# nixie_main_controller_board_0_2_3.net
KiCad netlist of a schematic drawn in EAGLE
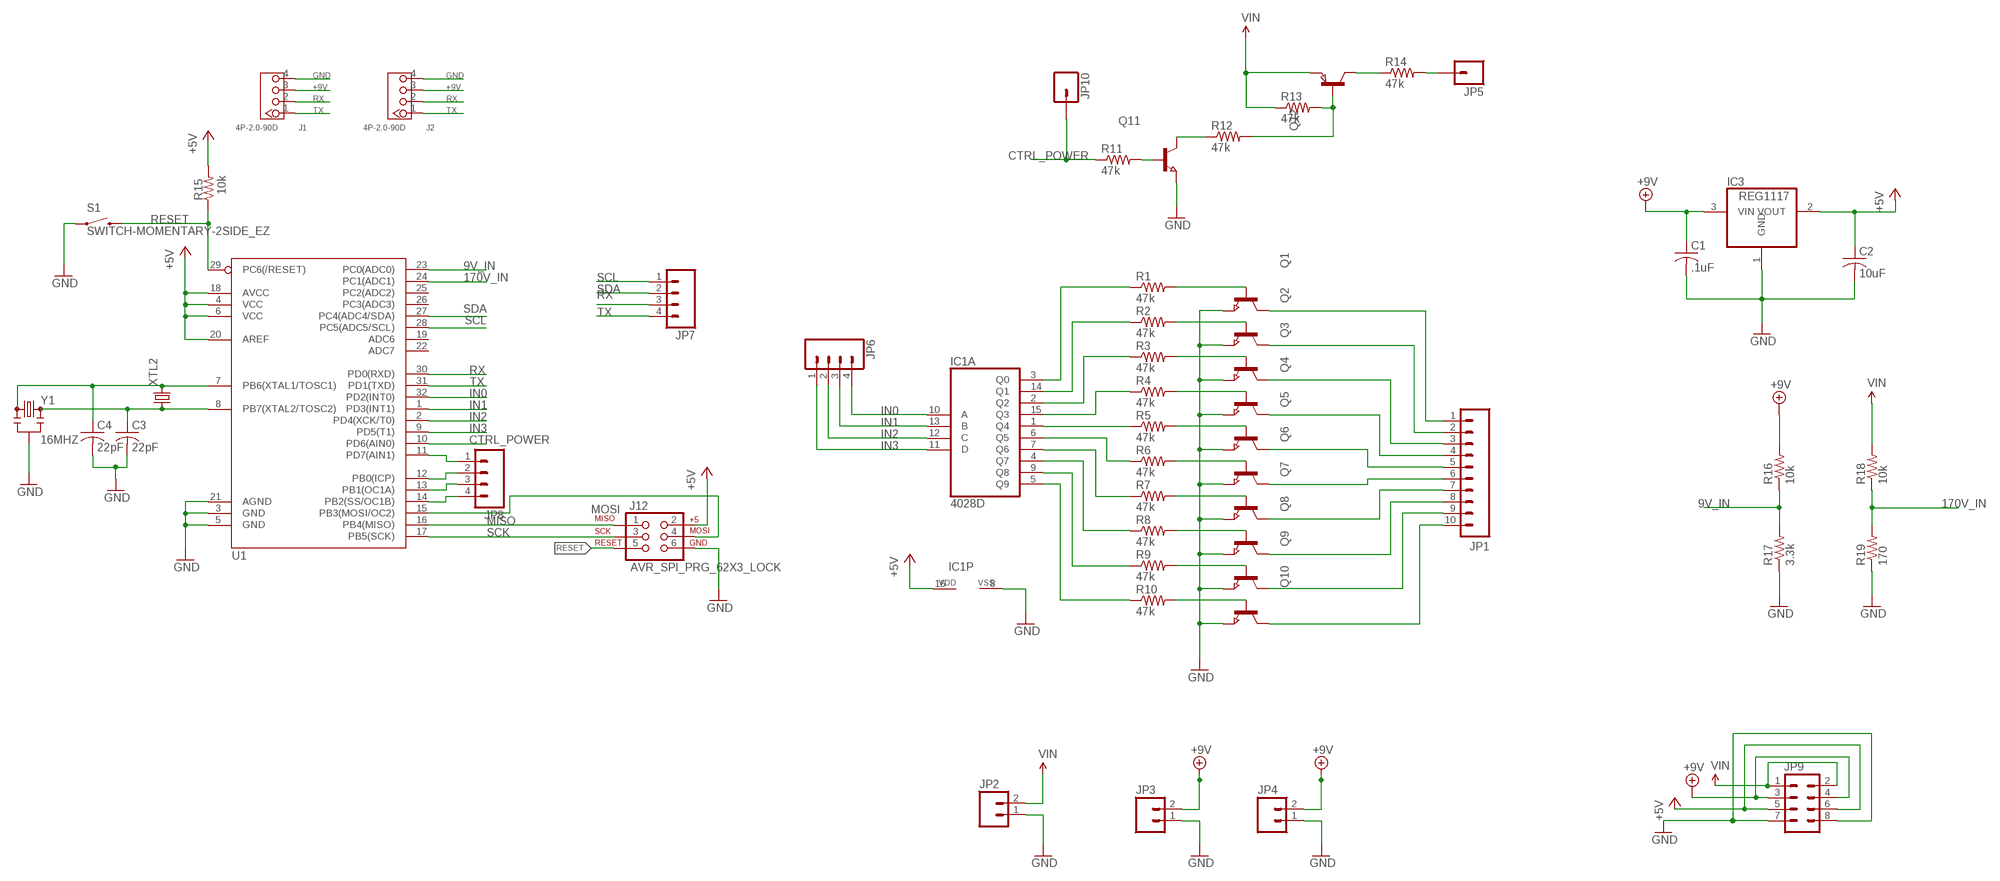
[diagram p0: schematic, sheet 1]

(export (version "E")
  (design (tool "Eeschema 10.0.6"))
  (components
    (comp (ref "C1")
      (value ".1uF")
      (footprint "eagle-import:C0603")
      (libsource (lib "eagle-import") (part "C-USC0603"))
    )
    (comp (ref "C2")
      (value "10uF")
      (footprint "eagle-import:C0805")
      (libsource (lib "eagle-import") (part "C-USC0805"))
    )
    (comp (ref "C3")
      (value "22pF")
      (footprint "eagle-import:C0603")
      (libsource (lib "eagle-import") (part "C-USC0603"))
    )
    (comp (ref "C4")
      (value "22pF")
      (footprint "eagle-import:C0603")
      (libsource (lib "eagle-import") (part "C-USC0603"))
    )
    (comp (ref "IC1")
      (value "4028D")
      (footprint "eagle-import:SO16")
      (libsource (lib "eagle-import") (part "4028D"))
    )
    (comp (ref "IC3")
      (value "REG1117")
      (footprint "eagle-import:SOT223")
      (libsource (lib "eagle-import") (part "REG1117"))
    )
    (comp (ref "J1")
      (value "4P-2.0-90D")
      (footprint "eagle-import:HW4-2.0-90D")
      (libsource (lib "eagle-import") (part "GROVE-CONNECTOR-DIP-90D(4P-2.0)"))
    )
    (comp (ref "J2")
      (value "4P-2.0-90D")
      (footprint "eagle-import:HW4-2.0-90D")
      (libsource (lib "eagle-import") (part "GROVE-CONNECTOR-DIP-90D(4P-2.0)"))
    )
    (comp (ref "J12")
      (value "AVR_SPI_PRG_62X3_LOCK")
      (footprint "eagle-import:2X3_LOCK")
      (libsource (lib "eagle-import") (part "AVR_SPI_PRG_62X3_LOCK"))
    )
    (comp (ref "JP1")
      (value "M10LOCK")
      (footprint "eagle-import:1X10_LOCK")
      (libsource (lib "eagle-import") (part "M10LOCK"))
    )
    (comp (ref "JP2")
      (value "M02LOCK")
      (footprint "eagle-import:1X02_LOCK")
      (libsource (lib "eagle-import") (part "M02LOCK"))
    )
    (comp (ref "JP3")
      (value "M02LOCK")
      (footprint "eagle-import:1X02_LOCK")
      (libsource (lib "eagle-import") (part "M02LOCK"))
    )
    (comp (ref "JP4")
      (value "M02LOCK")
      (footprint "eagle-import:1X02_LOCK")
      (libsource (lib "eagle-import") (part "M02LOCK"))
    )
    (comp (ref "JP5")
      (value "M01PTH")
      (footprint "eagle-import:1X01")
      (libsource (lib "eagle-import") (part "M01PTH"))
    )
    (comp (ref "JP6")
      (value "M04PTH")
      (footprint "eagle-import:1X04")
      (libsource (lib "eagle-import") (part "M04PTH"))
    )
    (comp (ref "JP7")
      (value "M04PTH")
      (footprint "eagle-import:1X04")
      (libsource (lib "eagle-import") (part "M04PTH"))
    )
    (comp (ref "JP8")
      (value "M04PTH")
      (footprint "eagle-import:1X04")
      (libsource (lib "eagle-import") (part "M04PTH"))
    )
    (comp (ref "JP9")
      (value "M04X2")
      (footprint "eagle-import:2X4")
      (libsource (lib "eagle-import") (part "M04X2"))
    )
    (comp (ref "JP10")
      (value "M01PTH")
      (footprint "eagle-import:1X01")
      (libsource (lib "eagle-import") (part "M01PTH"))
    )
    (comp (ref "Q1")
      (value "NPN-TRANSISTOR_SOT23")
      (footprint "eagle-import:SOT23")
      (libsource (lib "eagle-import") (part "NPN-TRANSISTOR_SOT23"))
    )
    (comp (ref "Q2")
      (value "NPN-TRANSISTOR_SOT23")
      (footprint "eagle-import:SOT23")
      (libsource (lib "eagle-import") (part "NPN-TRANSISTOR_SOT23"))
    )
    (comp (ref "Q3")
      (value "NPN-TRANSISTOR_SOT23")
      (footprint "eagle-import:SOT23")
      (libsource (lib "eagle-import") (part "NPN-TRANSISTOR_SOT23"))
    )
    (comp (ref "Q4")
      (value "NPN-TRANSISTOR_SOT23")
      (footprint "eagle-import:SOT23")
      (libsource (lib "eagle-import") (part "NPN-TRANSISTOR_SOT23"))
    )
    (comp (ref "Q5")
      (value "NPN-TRANSISTOR_SOT23")
      (footprint "eagle-import:SOT23")
      (libsource (lib "eagle-import") (part "NPN-TRANSISTOR_SOT23"))
    )
    (comp (ref "Q6")
      (value "NPN-TRANSISTOR_SOT23")
      (footprint "eagle-import:SOT23")
      (libsource (lib "eagle-import") (part "NPN-TRANSISTOR_SOT23"))
    )
    (comp (ref "Q7")
      (value "NPN-TRANSISTOR_SOT23")
      (footprint "eagle-import:SOT23")
      (libsource (lib "eagle-import") (part "NPN-TRANSISTOR_SOT23"))
    )
    (comp (ref "Q8")
      (value "NPN-TRANSISTOR_SOT23")
      (footprint "eagle-import:SOT23")
      (libsource (lib "eagle-import") (part "NPN-TRANSISTOR_SOT23"))
    )
    (comp (ref "Q9")
      (value "NPN-TRANSISTOR_SOT23")
      (footprint "eagle-import:SOT23")
      (libsource (lib "eagle-import") (part "NPN-TRANSISTOR_SOT23"))
    )
    (comp (ref "Q10")
      (value "NPN-TRANSISTOR_SOT23")
      (footprint "eagle-import:SOT23")
      (libsource (lib "eagle-import") (part "NPN-TRANSISTOR_SOT23"))
    )
    (comp (ref "Q11")
      (value "NPN-TRANSISTOR_SOT23")
      (footprint "eagle-import:SOT23")
      (libsource (lib "eagle-import") (part "NPN-TRANSISTOR_SOT23"))
    )
    (comp (ref "Q12")
      (value "PNP-TRANSISTOR_SOT23")
      (footprint "eagle-import:SOT23")
      (libsource (lib "eagle-import") (part "PNP-TRANSISTOR_SOT23"))
    )
    (comp (ref "R1")
      (value "47k")
      (footprint "eagle-import:R0603")
      (libsource (lib "eagle-import") (part "rcl_R-US_R0603"))
    )
    (comp (ref "R2")
      (value "47k")
      (footprint "eagle-import:R0603")
      (libsource (lib "eagle-import") (part "rcl_R-US_R0603"))
    )
    (comp (ref "R3")
      (value "47k")
      (footprint "eagle-import:R0603")
      (libsource (lib "eagle-import") (part "rcl_R-US_R0603"))
    )
    (comp (ref "R4")
      (value "47k")
      (footprint "eagle-import:R0603")
      (libsource (lib "eagle-import") (part "rcl_R-US_R0603"))
    )
    (comp (ref "R5")
      (value "47k")
      (footprint "eagle-import:R0603")
      (libsource (lib "eagle-import") (part "rcl_R-US_R0603"))
    )
    (comp (ref "R6")
      (value "47k")
      (footprint "eagle-import:R0603")
      (libsource (lib "eagle-import") (part "rcl_R-US_R0603"))
    )
    (comp (ref "R7")
      (value "47k")
      (footprint "eagle-import:R0603")
      (libsource (lib "eagle-import") (part "rcl_R-US_R0603"))
    )
    (comp (ref "R8")
      (value "47k")
      (footprint "eagle-import:R0603")
      (libsource (lib "eagle-import") (part "rcl_R-US_R0603"))
    )
    (comp (ref "R9")
      (value "47k")
      (footprint "eagle-import:R0603")
      (libsource (lib "eagle-import") (part "rcl_R-US_R0603"))
    )
    (comp (ref "R10")
      (value "47k")
      (footprint "eagle-import:R0603")
      (libsource (lib "eagle-import") (part "rcl_R-US_R0603"))
    )
    (comp (ref "R11")
      (value "47k")
      (footprint "eagle-import:R0603")
      (libsource (lib "eagle-import") (part "rcl_R-US_R0603"))
    )
    (comp (ref "R12")
      (value "47k")
      (footprint "eagle-import:R0603")
      (libsource (lib "eagle-import") (part "rcl_R-US_R0603"))
    )
    (comp (ref "R13")
      (value "47k")
      (footprint "eagle-import:R0603")
      (libsource (lib "eagle-import") (part "rcl_R-US_R0603"))
    )
    (comp (ref "R14")
      (value "47k")
      (footprint "eagle-import:R0603")
      (libsource (lib "eagle-import") (part "rcl_R-US_R0603"))
    )
    (comp (ref "R15")
      (value "10k")
      (footprint "eagle-import:0603")
      (libsource (lib "eagle-import") (part "RESISTOR0603-RES"))
    )
    (comp (ref "R16")
      (value "10k")
      (footprint "eagle-import:R0603")
      (libsource (lib "eagle-import") (part "rcl_R-US_R0603"))
    )
    (comp (ref "R17")
      (value "3.3k")
      (footprint "eagle-import:R0603")
      (libsource (lib "eagle-import") (part "rcl_R-US_R0603"))
    )
    (comp (ref "R18")
      (value "10k")
      (footprint "eagle-import:R0603")
      (libsource (lib "eagle-import") (part "rcl_R-US_R0603"))
    )
    (comp (ref "R19")
      (value "170")
      (footprint "eagle-import:M1206")
      (libsource (lib "eagle-import") (part "R-US_M1206"))
    )
    (comp (ref "S1")
      (value "SWITCH-MOMENTARY-2SIDE_EZ")
      (footprint "eagle-import:TACTILE-PTH-SIDEEZ")
      (libsource (lib "eagle-import") (part "SWITCH-MOMENTARY-2SIDE_EZ"))
    )
    (comp (ref "U1")
      (value "ATMEGA328_SMT")
      (footprint "eagle-import:TQFP32-08")
      (libsource (lib "eagle-import") (part "ATMEGA328_SMT"))
    )
    (comp (ref "XTL2")
      (value "CRYSTALHC49S")
      (footprint "eagle-import:HC49_S")
      (libsource (lib "eagle-import") (part "CRYSTALHC49S"))
    )
    (comp (ref "Y1")
      (value "16MHZ")
      (footprint "eagle-import:RESONATOR-SMD")
      (libsource (lib "eagle-import") (part "RESONATOR16MHZ"))
    )
  )
  (nets
    (net (code "1") (name "+5V") (class "Default")
      (node (ref "C2") (pin "1") (pinfunction "1_1") (pintype "passive"))
      (node (ref "IC1") (pin "16") (pinfunction "VDD_16") (pintype "power_in"))
      (node (ref "IC3") (pin "2") (pinfunction "VOUT_2") (pintype "output"))
      (node (ref "J12") (pin "2") (pinfunction "2_2") (pintype "passive"))
      (node (ref "JP9") (pin "5") (pinfunction "5_5") (pintype "passive"))
      (node (ref "JP9") (pin "6") (pinfunction "6_6") (pintype "passive"))
      (node (ref "R15") (pin "2") (pinfunction "2_2") (pintype "passive"))
      (node (ref "U1") (pin "18") (pinfunction "AVCC_18") (pintype "bidirectional"))
      (node (ref "U1") (pin "20") (pinfunction "AREF_20") (pintype "bidirectional"))
      (node (ref "U1") (pin "4") (pinfunction "VCC_4") (pintype "bidirectional"))
      (node (ref "U1") (pin "6") (pinfunction "VCC_6") (pintype "bidirectional"))
    )
    (net (code "2") (name "+9V") (class "Default")
      (node (ref "C1") (pin "1") (pinfunction "1_1") (pintype "passive"))
      (node (ref "IC3") (pin "3") (pinfunction "VIN_3") (pintype "input"))
      (node (ref "J1") (pin "3") (pinfunction "3_3") (pintype "bidirectional"))
      (node (ref "J2") (pin "3") (pinfunction "3_3") (pintype "bidirectional"))
      (node (ref "JP3") (pin "2") (pinfunction "2_2") (pintype "passive"))
      (node (ref "JP4") (pin "2") (pinfunction "2_2") (pintype "passive"))
      (node (ref "JP9") (pin "3") (pinfunction "3_3") (pintype "passive"))
      (node (ref "JP9") (pin "4") (pinfunction "4_4") (pintype "passive"))
      (node (ref "R16") (pin "2") (pinfunction "2_2") (pintype "passive"))
    )
    (net (code "3") (name "/9V_IN") (class "Default")
      (node (ref "R16") (pin "1") (pinfunction "1_1") (pintype "passive"))
      (node (ref "R17") (pin "2") (pinfunction "2_2") (pintype "passive"))
      (node (ref "U1") (pin "23") (pinfunction "PC0(ADC0)_23") (pintype "bidirectional"))
    )
    (net (code "4") (name "/170V_IN") (class "Default")
      (node (ref "R18") (pin "1") (pinfunction "1_1") (pintype "passive"))
      (node (ref "R19") (pin "2") (pinfunction "2_2") (pintype "passive"))
      (node (ref "U1") (pin "24") (pinfunction "PC1(ADC1)_24") (pintype "bidirectional"))
    )
    (net (code "5") (name "/CTRL_POWER") (class "Default")
      (node (ref "JP10") (pin "1") (pinfunction "1_1") (pintype "passive"))
      (node (ref "R11") (pin "1") (pinfunction "1_1") (pintype "passive"))
      (node (ref "U1") (pin "10") (pinfunction "PD6(AIN0)_10") (pintype "bidirectional"))
    )
    (net (code "6") (name "/IN0") (class "Default")
      (node (ref "IC1") (pin "10") (pinfunction "A_10") (pintype "input"))
      (node (ref "JP6") (pin "4") (pinfunction "4_4") (pintype "passive"))
      (node (ref "U1") (pin "32") (pinfunction "PD2(INT0)_32") (pintype "bidirectional"))
    )
    (net (code "7") (name "/IN1") (class "Default")
      (node (ref "IC1") (pin "13") (pinfunction "B_13") (pintype "input"))
      (node (ref "JP6") (pin "3") (pinfunction "3_3") (pintype "passive"))
      (node (ref "U1") (pin "1") (pinfunction "PD3(INT1)_1") (pintype "bidirectional"))
    )
    (net (code "8") (name "/IN2") (class "Default")
      (node (ref "IC1") (pin "12") (pinfunction "C_12") (pintype "input"))
      (node (ref "JP6") (pin "2") (pinfunction "2_2") (pintype "passive"))
      (node (ref "U1") (pin "2") (pinfunction "PD4(XCK/T0)_2") (pintype "bidirectional"))
    )
    (net (code "9") (name "/IN3") (class "Default")
      (node (ref "IC1") (pin "11") (pinfunction "D_11") (pintype "input"))
      (node (ref "JP6") (pin "1") (pinfunction "1_1") (pintype "passive"))
      (node (ref "U1") (pin "9") (pinfunction "PD5(T1)_9") (pintype "bidirectional"))
    )
    (net (code "10") (name "/MISO") (class "Default")
      (node (ref "J12") (pin "1") (pinfunction "1_1") (pintype "passive"))
      (node (ref "U1") (pin "16") (pinfunction "PB4(MISO)_16") (pintype "bidirectional"))
    )
    (net (code "11") (name "/MOSI") (class "Default")
      (node (ref "J12") (pin "4") (pinfunction "4_4") (pintype "passive"))
      (node (ref "U1") (pin "15") (pinfunction "PB3(MOSI/OC2)_15") (pintype "bidirectional"))
    )
    (net (code "12") (name "/RX") (class "Default")
      (node (ref "J1") (pin "2") (pinfunction "2_2") (pintype "bidirectional"))
      (node (ref "J2") (pin "2") (pinfunction "2_2") (pintype "bidirectional"))
      (node (ref "JP7") (pin "3") (pinfunction "3_3") (pintype "passive"))
      (node (ref "U1") (pin "30") (pinfunction "PD0(RXD)_30") (pintype "bidirectional"))
    )
    (net (code "13") (name "/SCK") (class "Default")
      (node (ref "J12") (pin "3") (pinfunction "3_3") (pintype "passive"))
      (node (ref "U1") (pin "17") (pinfunction "PB5(SCK)_17") (pintype "bidirectional"))
    )
    (net (code "14") (name "/SCL") (class "Default")
      (node (ref "JP7") (pin "1") (pinfunction "1_1") (pintype "passive"))
      (node (ref "U1") (pin "28") (pinfunction "PC5(ADC5/SCL)_28") (pintype "bidirectional"))
    )
    (net (code "15") (name "/SDA") (class "Default")
      (node (ref "JP7") (pin "2") (pinfunction "2_2") (pintype "passive"))
      (node (ref "U1") (pin "27") (pinfunction "PC4(ADC4/SDA)_27") (pintype "bidirectional"))
    )
    (net (code "16") (name "/TX") (class "Default")
      (node (ref "J1") (pin "1") (pinfunction "1_1") (pintype "bidirectional"))
      (node (ref "J2") (pin "1") (pinfunction "1_1") (pintype "bidirectional"))
      (node (ref "JP7") (pin "4") (pinfunction "4_4") (pintype "passive"))
      (node (ref "U1") (pin "31") (pinfunction "PD1(TXD)_31") (pintype "bidirectional"))
    )
    (net (code "17") (name "GND") (class "Default")
      (node (ref "C1") (pin "2") (pinfunction "2_2") (pintype "passive"))
      (node (ref "C2") (pin "2") (pinfunction "2_2") (pintype "passive"))
      (node (ref "C3") (pin "2") (pinfunction "2_2") (pintype "passive"))
      (node (ref "C4") (pin "2") (pinfunction "2_2") (pintype "passive"))
      (node (ref "IC1") (pin "8") (pinfunction "VSS_8") (pintype "power_in"))
      (node (ref "IC3") (pin "1") (pinfunction "GND_1") (pintype "power_in"))
      (node (ref "J1") (pin "4") (pinfunction "4_4") (pintype "bidirectional"))
      (node (ref "J12") (pin "6") (pinfunction "6_6") (pintype "passive"))
      (node (ref "J2") (pin "4") (pinfunction "4_4") (pintype "bidirectional"))
      (node (ref "JP2") (pin "1") (pinfunction "1_1") (pintype "passive"))
      (node (ref "JP3") (pin "1") (pinfunction "1_1") (pintype "passive"))
      (node (ref "JP4") (pin "1") (pinfunction "1_1") (pintype "passive"))
      (node (ref "JP9") (pin "7") (pinfunction "7_7") (pintype "passive"))
      (node (ref "JP9") (pin "8") (pinfunction "8_8") (pintype "passive"))
      (node (ref "Q1") (pin "2") (pinfunction "E_2") (pintype "passive"))
      (node (ref "Q10") (pin "2") (pinfunction "E_2") (pintype "passive"))
      (node (ref "Q11") (pin "2") (pinfunction "E_2") (pintype "passive"))
      (node (ref "Q2") (pin "2") (pinfunction "E_2") (pintype "passive"))
      (node (ref "Q3") (pin "2") (pinfunction "E_2") (pintype "passive"))
      (node (ref "Q4") (pin "2") (pinfunction "E_2") (pintype "passive"))
      (node (ref "Q5") (pin "2") (pinfunction "E_2") (pintype "passive"))
      (node (ref "Q6") (pin "2") (pinfunction "E_2") (pintype "passive"))
      (node (ref "Q7") (pin "2") (pinfunction "E_2") (pintype "passive"))
      (node (ref "Q8") (pin "2") (pinfunction "E_2") (pintype "passive"))
      (node (ref "Q9") (pin "2") (pinfunction "E_2") (pintype "passive"))
      (node (ref "R17") (pin "1") (pinfunction "1_1") (pintype "passive"))
      (node (ref "R19") (pin "1") (pinfunction "1_1") (pintype "passive"))
      (node (ref "S1") (pin "1") (pinfunction "1_1") (pintype "passive"))
      (node (ref "U1") (pin "21") (pinfunction "AGND_21") (pintype "bidirectional"))
      (node (ref "U1") (pin "3") (pinfunction "GND_3") (pintype "bidirectional"))
      (node (ref "U1") (pin "5") (pinfunction "GND_5") (pintype "bidirectional"))
      (node (ref "Y1") (pin "2") (pinfunction "2_2") (pintype "passive"))
    )
    (net (code "18") (name "Net-(IC1A-Q0)") (class "Default")
      (node (ref "IC1") (pin "3") (pinfunction "Q0_3") (pintype "output"))
      (node (ref "R1") (pin "1") (pinfunction "1_1") (pintype "passive"))
    )
    (net (code "19") (name "Net-(IC1A-Q1)") (class "Default")
      (node (ref "IC1") (pin "14") (pinfunction "Q1_14") (pintype "output"))
      (node (ref "R2") (pin "1") (pinfunction "1_1") (pintype "passive"))
    )
    (net (code "20") (name "Net-(IC1A-Q2)") (class "Default")
      (node (ref "IC1") (pin "2") (pinfunction "Q2_2") (pintype "output"))
      (node (ref "R3") (pin "1") (pinfunction "1_1") (pintype "passive"))
    )
    (net (code "21") (name "Net-(IC1A-Q3)") (class "Default")
      (node (ref "IC1") (pin "15") (pinfunction "Q3_15") (pintype "output"))
      (node (ref "R4") (pin "1") (pinfunction "1_1") (pintype "passive"))
    )
    (net (code "22") (name "Net-(IC1A-Q4)") (class "Default")
      (node (ref "IC1") (pin "1") (pinfunction "Q4_1") (pintype "output"))
      (node (ref "R5") (pin "1") (pinfunction "1_1") (pintype "passive"))
    )
    (net (code "23") (name "Net-(IC1A-Q5)") (class "Default")
      (node (ref "IC1") (pin "6") (pinfunction "Q5_6") (pintype "output"))
      (node (ref "R6") (pin "1") (pinfunction "1_1") (pintype "passive"))
    )
    (net (code "24") (name "Net-(IC1A-Q6)") (class "Default")
      (node (ref "IC1") (pin "7") (pinfunction "Q6_7") (pintype "output"))
      (node (ref "R7") (pin "1") (pinfunction "1_1") (pintype "passive"))
    )
    (net (code "25") (name "Net-(IC1A-Q7)") (class "Default")
      (node (ref "IC1") (pin "4") (pinfunction "Q7_4") (pintype "output"))
      (node (ref "R8") (pin "1") (pinfunction "1_1") (pintype "passive"))
    )
    (net (code "26") (name "Net-(IC1A-Q8)") (class "Default")
      (node (ref "IC1") (pin "9") (pinfunction "Q8_9") (pintype "output"))
      (node (ref "R9") (pin "1") (pinfunction "1_1") (pintype "passive"))
    )
    (net (code "27") (name "Net-(IC1A-Q9)") (class "Default")
      (node (ref "IC1") (pin "5") (pinfunction "Q9_5") (pintype "output"))
      (node (ref "R10") (pin "1") (pinfunction "1_1") (pintype "passive"))
    )
    (net (code "28") (name "Net-(JP5-Pad1)") (class "Default")
      (node (ref "JP5") (pin "1") (pinfunction "1_1") (pintype "passive"))
      (node (ref "R14") (pin "2") (pinfunction "2_2") (pintype "passive"))
    )
    (net (code "29") (name "Net-(Q1-B)") (class "Default")
      (node (ref "Q1") (pin "1") (pinfunction "B_1") (pintype "passive"))
      (node (ref "R1") (pin "2") (pinfunction "2_2") (pintype "passive"))
    )
    (net (code "30") (name "Net-(Q1-C)") (class "Default")
      (node (ref "JP1") (pin "1") (pinfunction "1_1") (pintype "passive"))
      (node (ref "Q1") (pin "3") (pinfunction "C_3") (pintype "passive"))
    )
    (net (code "31") (name "Net-(Q2-B)") (class "Default")
      (node (ref "Q2") (pin "1") (pinfunction "B_1") (pintype "passive"))
      (node (ref "R2") (pin "2") (pinfunction "2_2") (pintype "passive"))
    )
    (net (code "32") (name "Net-(Q2-C)") (class "Default")
      (node (ref "JP1") (pin "2") (pinfunction "2_2") (pintype "passive"))
      (node (ref "Q2") (pin "3") (pinfunction "C_3") (pintype "passive"))
    )
    (net (code "33") (name "Net-(Q3-B)") (class "Default")
      (node (ref "Q3") (pin "1") (pinfunction "B_1") (pintype "passive"))
      (node (ref "R3") (pin "2") (pinfunction "2_2") (pintype "passive"))
    )
    (net (code "34") (name "Net-(Q3-C)") (class "Default")
      (node (ref "JP1") (pin "3") (pinfunction "3_3") (pintype "passive"))
      (node (ref "Q3") (pin "3") (pinfunction "C_3") (pintype "passive"))
    )
    (net (code "35") (name "Net-(Q4-B)") (class "Default")
      (node (ref "Q4") (pin "1") (pinfunction "B_1") (pintype "passive"))
      (node (ref "R4") (pin "2") (pinfunction "2_2") (pintype "passive"))
    )
    (net (code "36") (name "Net-(Q4-C)") (class "Default")
      (node (ref "JP1") (pin "4") (pinfunction "4_4") (pintype "passive"))
      (node (ref "Q4") (pin "3") (pinfunction "C_3") (pintype "passive"))
    )
    (net (code "37") (name "Net-(Q5-B)") (class "Default")
      (node (ref "Q5") (pin "1") (pinfunction "B_1") (pintype "passive"))
      (node (ref "R5") (pin "2") (pinfunction "2_2") (pintype "passive"))
    )
    (net (code "38") (name "Net-(Q5-C)") (class "Default")
      (node (ref "JP1") (pin "5") (pinfunction "5_5") (pintype "passive"))
      (node (ref "Q5") (pin "3") (pinfunction "C_3") (pintype "passive"))
    )
    (net (code "39") (name "Net-(Q6-B)") (class "Default")
      (node (ref "Q6") (pin "1") (pinfunction "B_1") (pintype "passive"))
      (node (ref "R6") (pin "2") (pinfunction "2_2") (pintype "passive"))
    )
    (net (code "40") (name "Net-(Q6-C)") (class "Default")
      (node (ref "JP1") (pin "6") (pinfunction "6_6") (pintype "passive"))
      (node (ref "Q6") (pin "3") (pinfunction "C_3") (pintype "passive"))
    )
    (net (code "41") (name "Net-(Q7-B)") (class "Default")
      (node (ref "Q7") (pin "1") (pinfunction "B_1") (pintype "passive"))
      (node (ref "R7") (pin "2") (pinfunction "2_2") (pintype "passive"))
    )
    (net (code "42") (name "Net-(Q7-C)") (class "Default")
      (node (ref "JP1") (pin "7") (pinfunction "7_7") (pintype "passive"))
      (node (ref "Q7") (pin "3") (pinfunction "C_3") (pintype "passive"))
    )
    (net (code "43") (name "Net-(Q8-B)") (class "Default")
      (node (ref "Q8") (pin "1") (pinfunction "B_1") (pintype "passive"))
      (node (ref "R8") (pin "2") (pinfunction "2_2") (pintype "passive"))
    )
    (net (code "44") (name "Net-(Q8-C)") (class "Default")
      (node (ref "JP1") (pin "8") (pinfunction "8_8") (pintype "passive"))
      (node (ref "Q8") (pin "3") (pinfunction "C_3") (pintype "passive"))
    )
    (net (code "45") (name "Net-(Q9-B)") (class "Default")
      (node (ref "Q9") (pin "1") (pinfunction "B_1") (pintype "passive"))
      (node (ref "R9") (pin "2") (pinfunction "2_2") (pintype "passive"))
    )
    (net (code "46") (name "Net-(Q9-C)") (class "Default")
      (node (ref "JP1") (pin "9") (pinfunction "9_9") (pintype "passive"))
      (node (ref "Q9") (pin "3") (pinfunction "C_3") (pintype "passive"))
    )
    (net (code "47") (name "Net-(Q10-B)") (class "Default")
      (node (ref "Q10") (pin "1") (pinfunction "B_1") (pintype "passive"))
      (node (ref "R10") (pin "2") (pinfunction "2_2") (pintype "passive"))
    )
    (net (code "48") (name "Net-(Q10-C)") (class "Default")
      (node (ref "JP1") (pin "10") (pinfunction "10_10") (pintype "passive"))
      (node (ref "Q10") (pin "3") (pinfunction "C_3") (pintype "passive"))
    )
    (net (code "49") (name "Net-(Q11-B)") (class "Default")
      (node (ref "Q11") (pin "1") (pinfunction "B_1") (pintype "passive"))
      (node (ref "R11") (pin "2") (pinfunction "2_2") (pintype "passive"))
    )
    (net (code "50") (name "Net-(Q11-C)") (class "Default")
      (node (ref "Q11") (pin "3") (pinfunction "C_3") (pintype "passive"))
      (node (ref "R12") (pin "1") (pinfunction "1_1") (pintype "passive"))
    )
    (net (code "51") (name "Net-(Q12-B)") (class "Default")
      (node (ref "Q12") (pin "1") (pinfunction "B_1") (pintype "passive"))
      (node (ref "R12") (pin "2") (pinfunction "2_2") (pintype "passive"))
      (node (ref "R13") (pin "2") (pinfunction "2_2") (pintype "passive"))
    )
    (net (code "52") (name "Net-(Q12-C)") (class "Default")
      (node (ref "Q12") (pin "3") (pinfunction "C_3") (pintype "passive"))
      (node (ref "R14") (pin "1") (pinfunction "1_1") (pintype "passive"))
    )
    (net (code "53") (name "Net-(U1-PB0(ICP))") (class "Default")
      (node (ref "JP8") (pin "2") (pinfunction "2_2") (pintype "passive"))
      (node (ref "U1") (pin "12") (pinfunction "PB0(ICP)_12") (pintype "bidirectional"))
    )
    (net (code "54") (name "Net-(U1-PB1(OC1A))") (class "Default")
      (node (ref "JP8") (pin "3") (pinfunction "3_3") (pintype "passive"))
      (node (ref "U1") (pin "13") (pinfunction "PB1(OC1A)_13") (pintype "bidirectional"))
    )
    (net (code "55") (name "Net-(U1-PB2(SS{slash}OC1B))") (class "Default")
      (node (ref "JP8") (pin "4") (pinfunction "4_4") (pintype "passive"))
      (node (ref "U1") (pin "14") (pinfunction "PB2(SS/OC1B)_14") (pintype "bidirectional"))
    )
    (net (code "56") (name "Net-(U1-PB6(XTAL1{slash}TOSC1))") (class "Default")
      (node (ref "C4") (pin "1") (pinfunction "1_1") (pintype "passive"))
      (node (ref "U1") (pin "7") (pinfunction "PB6(XTAL1/TOSC1)_7") (pintype "bidirectional"))
      (node (ref "XTL2") (pin "2") (pinfunction "2_2") (pintype "passive"))
      (node (ref "Y1") (pin "1") (pinfunction "1_1") (pintype "passive"))
    )
    (net (code "57") (name "Net-(U1-PB7(XTAL2{slash}TOSC2))") (class "Default")
      (node (ref "C3") (pin "1") (pinfunction "1_1") (pintype "passive"))
      (node (ref "U1") (pin "8") (pinfunction "PB7(XTAL2/TOSC2)_8") (pintype "bidirectional"))
      (node (ref "XTL2") (pin "1") (pinfunction "1_1") (pintype "passive"))
      (node (ref "Y1") (pin "3") (pinfunction "3_3") (pintype "passive"))
    )
    (net (code "58") (name "Net-(U1-PD7(AIN1))") (class "Default")
      (node (ref "JP8") (pin "1") (pinfunction "1_1") (pintype "passive"))
      (node (ref "U1") (pin "11") (pinfunction "PD7(AIN1)_11") (pintype "bidirectional"))
    )
    (net (code "59") (name "RESET") (class "Default")
      (node (ref "J12") (pin "5") (pinfunction "5_5") (pintype "passive"))
      (node (ref "R15") (pin "1") (pinfunction "1_1") (pintype "passive"))
      (node (ref "S1") (pin "2") (pinfunction "2_2") (pintype "passive"))
      (node (ref "U1") (pin "29") (pinfunction "PC6(/RESET)_29") (pintype "bidirectional"))
    )
    (net (code "60") (name "VIN") (class "Default")
      (node (ref "JP2") (pin "2") (pinfunction "2_2") (pintype "passive"))
      (node (ref "JP9") (pin "1") (pinfunction "1_1") (pintype "passive"))
      (node (ref "JP9") (pin "2") (pinfunction "2_2") (pintype "passive"))
      (node (ref "Q12") (pin "2") (pinfunction "E_2") (pintype "passive"))
      (node (ref "R13") (pin "1") (pinfunction "1_1") (pintype "passive"))
      (node (ref "R18") (pin "2") (pinfunction "2_2") (pintype "passive"))
    )
    (net (code "61") (name "unconnected-(U1-ADC6-Pad19)") (class "Default")
      (node (ref "U1") (pin "19") (pinfunction "ADC6_19") (pintype "bidirectional"))
    )
    (net (code "62") (name "unconnected-(U1-ADC7-Pad22)") (class "Default")
      (node (ref "U1") (pin "22") (pinfunction "ADC7_22") (pintype "bidirectional"))
    )
    (net (code "63") (name "unconnected-(U1-PC2(ADC2)-Pad25)") (class "Default")
      (node (ref "U1") (pin "25") (pinfunction "PC2(ADC2)_25") (pintype "bidirectional"))
    )
    (net (code "64") (name "unconnected-(U1-PC3(ADC3)-Pad26)") (class "Default")
      (node (ref "U1") (pin "26") (pinfunction "PC3(ADC3)_26") (pintype "bidirectional"))
    )
  )
)
